# base-1.net
KiCad netlist of a schematic drawn in EAGLE
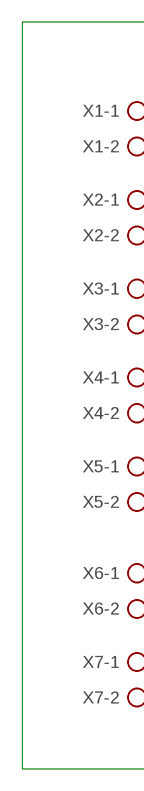
[diagram p0: schematic, sheet 1, part 1 of 2]
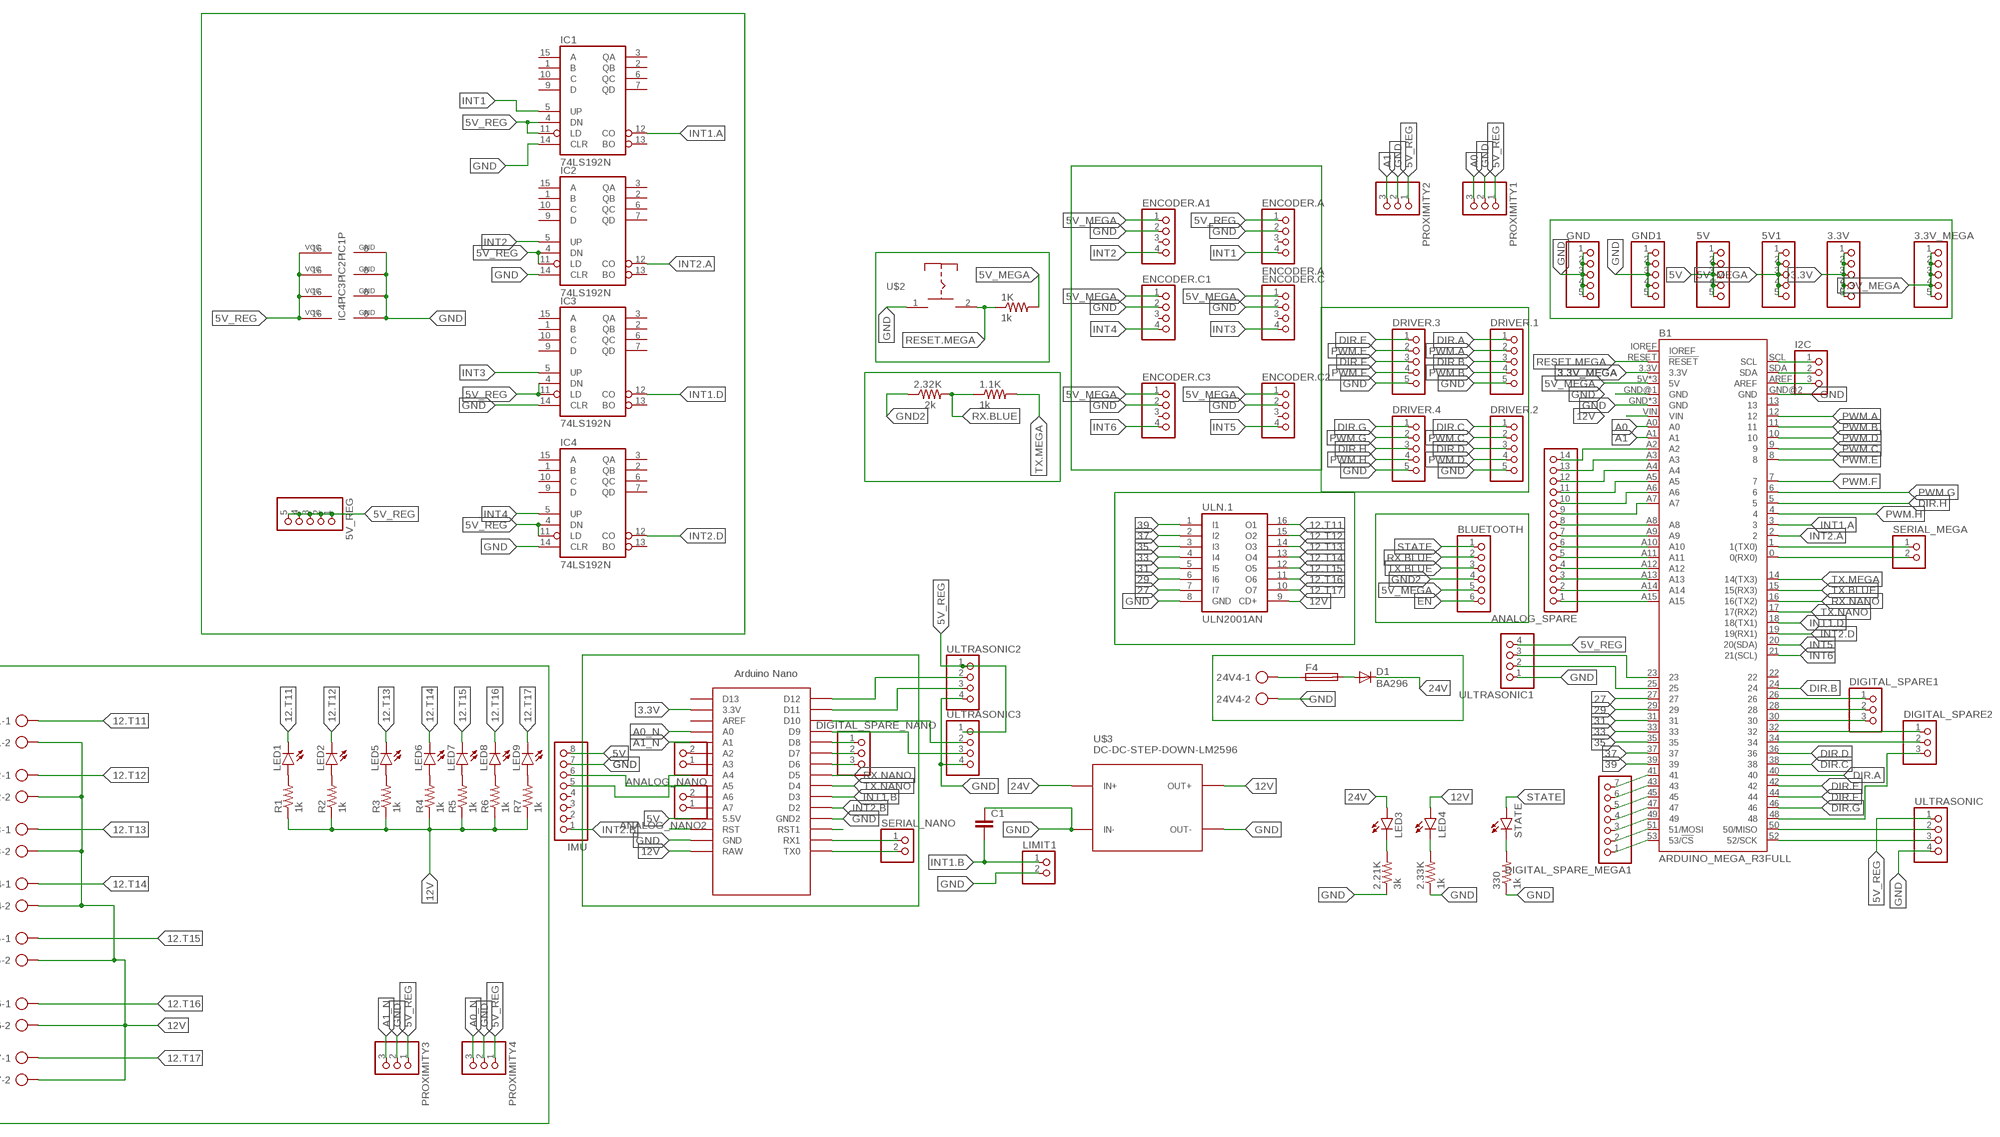
[diagram p1: schematic, sheet 1, part 2 of 2]

(export (version "E")
  (design (tool "Eeschema 10.0.6"))
  (components
    (comp (ref "1.1K")
      (value "1k")
      (footprint "eagle-import:0204_5")
      (libsource (lib "eagle-import") (part "R-US_0204/5"))
    )
    (comp (ref "1K")
      (value "1k")
      (footprint "eagle-import:0204_5")
      (libsource (lib "eagle-import") (part "R-US_0204/5"))
    )
    (comp (ref "2.21K")
      (value "3k")
      (footprint "eagle-import:0207_10")
      (libsource (lib "eagle-import") (part "R-US_0207/10"))
    )
    (comp (ref "2.32K")
      (value "2k")
      (footprint "eagle-import:0204_5")
      (libsource (lib "eagle-import") (part "R-US_0204/5"))
    )
    (comp (ref "2.33K")
      (value "1k")
      (footprint "eagle-import:0204_5")
      (libsource (lib "eagle-import") (part "R-US_0204/5"))
    )
    (comp (ref "3.3V")
      (value "PINHD-1X5")
      (footprint "eagle-import:1X05")
      (libsource (lib "eagle-import") (part "PINHD-1X5"))
    )
    (comp (ref "3.3V_MEGA")
      (value "PINHD-1X5")
      (footprint "eagle-import:1X05")
      (libsource (lib "eagle-import") (part "PINHD-1X5"))
    )
    (comp (ref "5V")
      (value "PINHD-1X5")
      (footprint "eagle-import:1X05")
      (libsource (lib "eagle-import") (part "PINHD-1X5"))
    )
    (comp (ref "5V1")
      (value "PINHD-1X5")
      (footprint "eagle-import:1X05")
      (libsource (lib "eagle-import") (part "PINHD-1X5"))
    )
    (comp (ref "5V_REG")
      (value "PINHD-1X5")
      (footprint "eagle-import:1X05")
      (libsource (lib "eagle-import") (part "PINHD-1X5"))
    )
    (comp (ref "24V4")
      (value "W237-113")
      (footprint "eagle-import:W237-113")
      (libsource (lib "eagle-import") (part "W237-113"))
    )
    (comp (ref "330")
      (value "1k")
      (footprint "eagle-import:0204_5")
      (libsource (lib "eagle-import") (part "R-US_0204/5"))
    )
    (comp (ref "ANALOG_NANO")
      (value "PINHD-1X2")
      (footprint "eagle-import:1X02")
      (libsource (lib "eagle-import") (part "PINHD-1X2"))
    )
    (comp (ref "ANALOG_NANO2")
      (value "PINHD-1X2")
      (footprint "eagle-import:1X02")
      (libsource (lib "eagle-import") (part "PINHD-1X2"))
    )
    (comp (ref "ANALOG_SPARE")
      (value "PINHD-1X14")
      (footprint "eagle-import:1X14")
      (libsource (lib "eagle-import") (part "PINHD-1X14"))
    )
    (comp (ref "B1")
      (value "ARDUINO_MEGA_R3FULL")
      (footprint "eagle-import:ARDUINO_MEGA_NO_SILK")
      (libsource (lib "eagle-import") (part "ARDUINO_MEGA_R3FULL"))
    )
    (comp (ref "BLUETOOTH")
      (value "PINHD-1X6")
      (footprint "eagle-import:1X06")
      (libsource (lib "eagle-import") (part "PINHD-1X6"))
    )
    (comp (ref "C1")
      (value "C-EU025-025X050")
      (footprint "eagle-import:C025-025X050")
      (libsource (lib "eagle-import") (part "C-EU025-025X050"))
    )
    (comp (ref "D1")
      (value "BA296")
      (footprint "eagle-import:P2-15")
      (libsource (lib "eagle-import") (part "BA296"))
    )
    (comp (ref "DIGITAL_SPARE1")
      (value "PINHD-1X3")
      (footprint "eagle-import:1X03")
      (libsource (lib "eagle-import") (part "PINHD-1X3"))
    )
    (comp (ref "DIGITAL_SPARE2")
      (value "PINHD-1X3")
      (footprint "eagle-import:1X03")
      (libsource (lib "eagle-import") (part "PINHD-1X3"))
    )
    (comp (ref "DIGITAL_SPARE_MEGA1")
      (value "PINHD-1X7")
      (footprint "eagle-import:1X07")
      (libsource (lib "eagle-import") (part "PINHD-1X7"))
    )
    (comp (ref "DIGITAL_SPARE_NANO")
      (value "PINHD-1X3")
      (footprint "eagle-import:1X03")
      (libsource (lib "eagle-import") (part "PINHD-1X3"))
    )
    (comp (ref "DRIVER.1")
      (value "PINHD-1X5")
      (footprint "eagle-import:1X05")
      (libsource (lib "eagle-import") (part "PINHD-1X5"))
    )
    (comp (ref "DRIVER.2")
      (value "PINHD-1X5")
      (footprint "eagle-import:1X05")
      (libsource (lib "eagle-import") (part "PINHD-1X5"))
    )
    (comp (ref "DRIVER.3")
      (value "PINHD-1X5")
      (footprint "eagle-import:1X05")
      (libsource (lib "eagle-import") (part "PINHD-1X5"))
    )
    (comp (ref "DRIVER.4")
      (value "PINHD-1X5")
      (footprint "eagle-import:1X05")
      (libsource (lib "eagle-import") (part "PINHD-1X5"))
    )
    (comp (ref "ENCODER.A")
      (value "ENCODER.A")
      (footprint "eagle-import:1X04")
      (libsource (lib "eagle-import") (part "PINHD-1X4"))
    )
    (comp (ref "ENCODER.A1")
      (value "PINHD-1X4")
      (footprint "eagle-import:1X04")
      (libsource (lib "eagle-import") (part "PINHD-1X4"))
    )
    (comp (ref "ENCODER.C")
      (value "PINHD-1X4")
      (footprint "eagle-import:1X04")
      (libsource (lib "eagle-import") (part "PINHD-1X4"))
    )
    (comp (ref "ENCODER.C1")
      (value "PINHD-1X4")
      (footprint "eagle-import:1X04")
      (libsource (lib "eagle-import") (part "PINHD-1X4"))
    )
    (comp (ref "ENCODER.C2")
      (value "PINHD-1X4")
      (footprint "eagle-import:1X04")
      (libsource (lib "eagle-import") (part "PINHD-1X4"))
    )
    (comp (ref "ENCODER.C3")
      (value "PINHD-1X4")
      (footprint "eagle-import:1X04")
      (libsource (lib "eagle-import") (part "PINHD-1X4"))
    )
    (comp (ref "F4")
      (value "SH22,5A")
      (footprint "eagle-import:SH22,5A")
      (fields (field (name "MPN") "0031.7701.11"))
      (libsource (lib "eagle-import") (part "SH22,5A"))
    )
    (comp (ref "GND")
      (value "PINHD-1X5")
      (footprint "eagle-import:1X05")
      (libsource (lib "eagle-import") (part "PINHD-1X5"))
    )
    (comp (ref "GND1")
      (value "PINHD-1X5")
      (footprint "eagle-import:1X05")
      (libsource (lib "eagle-import") (part "PINHD-1X5"))
    )
    (comp (ref "I2C")
      (value "PINHD-1X3")
      (footprint "eagle-import:1X03")
      (libsource (lib "eagle-import") (part "PINHD-1X3"))
    )
    (comp (ref "IC1")
      (value "74LS192N")
      (footprint "eagle-import:DIL16")
      (libsource (lib "eagle-import") (part "74192NLS"))
    )
    (comp (ref "IC2")
      (value "74LS192N")
      (footprint "eagle-import:DIL16")
      (libsource (lib "eagle-import") (part "74192NLS"))
    )
    (comp (ref "IC3")
      (value "74LS192N")
      (footprint "eagle-import:DIL16")
      (libsource (lib "eagle-import") (part "74192NLS"))
    )
    (comp (ref "IC4")
      (value "74LS192N")
      (footprint "eagle-import:DIL16")
      (libsource (lib "eagle-import") (part "74192NLS"))
    )
    (comp (ref "IMU")
      (value "PINHD-1X8")
      (footprint "eagle-import:1X08")
      (libsource (lib "eagle-import") (part "PINHD-1X8"))
    )
    (comp (ref "LED1")
      (value "LED3MM")
      (footprint "eagle-import:LED3MM")
      (libsource (lib "eagle-import") (part "LED3MM"))
    )
    (comp (ref "LED2")
      (value "LED3MM")
      (footprint "eagle-import:LED3MM")
      (libsource (lib "eagle-import") (part "LED3MM"))
    )
    (comp (ref "LED3")
      (value "LED5MM")
      (footprint "eagle-import:LED5MM")
      (libsource (lib "eagle-import") (part "LED5MM"))
    )
    (comp (ref "LED4")
      (value "LED5MM")
      (footprint "eagle-import:LED5MM")
      (libsource (lib "eagle-import") (part "LED5MM"))
    )
    (comp (ref "LED5")
      (value "LED3MM")
      (footprint "eagle-import:LED3MM")
      (libsource (lib "eagle-import") (part "LED3MM"))
    )
    (comp (ref "LED6")
      (value "LED3MM")
      (footprint "eagle-import:LED3MM")
      (libsource (lib "eagle-import") (part "LED3MM"))
    )
    (comp (ref "LED7")
      (value "LED3MM")
      (footprint "eagle-import:LED3MM")
      (libsource (lib "eagle-import") (part "LED3MM"))
    )
    (comp (ref "LED8")
      (value "LED3MM")
      (footprint "eagle-import:LED3MM")
      (libsource (lib "eagle-import") (part "LED3MM"))
    )
    (comp (ref "LED9")
      (value "LED3MM")
      (footprint "eagle-import:LED3MM")
      (libsource (lib "eagle-import") (part "LED3MM"))
    )
    (comp (ref "LIMIT1")
      (value "PINHD-1X2")
      (footprint "eagle-import:1X02")
      (libsource (lib "eagle-import") (part "PINHD-1X2"))
    )
    (comp (ref "PROXIMITY1")
      (value "PINHD-1X3")
      (footprint "eagle-import:1X03")
      (libsource (lib "eagle-import") (part "PINHD-1X3"))
    )
    (comp (ref "PROXIMITY2")
      (value "PINHD-1X3")
      (footprint "eagle-import:1X03")
      (libsource (lib "eagle-import") (part "PINHD-1X3"))
    )
    (comp (ref "PROXIMITY3")
      (value "PINHD-1X3")
      (footprint "eagle-import:1X03")
      (libsource (lib "eagle-import") (part "PINHD-1X3"))
    )
    (comp (ref "PROXIMITY4")
      (value "PINHD-1X3")
      (footprint "eagle-import:1X03")
      (libsource (lib "eagle-import") (part "PINHD-1X3"))
    )
    (comp (ref "R1")
      (value "1k")
      (footprint "eagle-import:0204_7")
      (libsource (lib "eagle-import") (part "R-US_0204/7"))
    )
    (comp (ref "R2")
      (value "1k")
      (footprint "eagle-import:0204_7")
      (libsource (lib "eagle-import") (part "R-US_0204/7"))
    )
    (comp (ref "R3")
      (value "1k")
      (footprint "eagle-import:0204_7")
      (libsource (lib "eagle-import") (part "R-US_0204/7"))
    )
    (comp (ref "R4")
      (value "1k")
      (footprint "eagle-import:0204_7")
      (libsource (lib "eagle-import") (part "R-US_0204/7"))
    )
    (comp (ref "R5")
      (value "1k")
      (footprint "eagle-import:0204_7")
      (libsource (lib "eagle-import") (part "R-US_0204/7"))
    )
    (comp (ref "R6")
      (value "1k")
      (footprint "eagle-import:0204_7")
      (libsource (lib "eagle-import") (part "R-US_0204/7"))
    )
    (comp (ref "R7")
      (value "1k")
      (footprint "eagle-import:0204_7")
      (libsource (lib "eagle-import") (part "R-US_0204/7"))
    )
    (comp (ref "SERIAL_MEGA")
      (value "PINHD-1X2")
      (footprint "eagle-import:1X02")
      (libsource (lib "eagle-import") (part "PINHD-1X2"))
    )
    (comp (ref "SERIAL_NANO")
      (value "PINHD-1X2")
      (footprint "eagle-import:1X02")
      (libsource (lib "eagle-import") (part "PINHD-1X2"))
    )
    (comp (ref "STATE")
      (value "LED3MM")
      (footprint "eagle-import:LED3MM")
      (libsource (lib "eagle-import") (part "LED3MM"))
    )
    (comp (ref "U$1")
      (value "NANO")
      (footprint "eagle-import:NANO")
      (libsource (lib "eagle-import") (part "NANO"))
    )
    (comp (ref "U$2")
      (value "PUSHBOTTON")
      (footprint "eagle-import:PUSHBOTTON")
      (libsource (lib "eagle-import") (part "PUSHBOTTON"))
    )
    (comp (ref "U$3")
      (value "DC-DC-STEP-DOWN-LM2596")
      (footprint "eagle-import:DC-DC-STEP-DOWN-LM2596")
      (libsource (lib "eagle-import") (part "DC-DC-STEP-DOWN-LM2596"))
    )
    (comp (ref "ULN.1")
      (value "ULN2001AN")
      (footprint "eagle-import:DIL16")
      (libsource (lib "eagle-import") (part "ULN2001AN"))
    )
    (comp (ref "ULTRASONIC")
      (value "PINHD-1X4")
      (footprint "eagle-import:1X04")
      (libsource (lib "eagle-import") (part "PINHD-1X4"))
    )
    (comp (ref "ULTRASONIC1")
      (value "PINHD-1X4")
      (footprint "eagle-import:1X04")
      (libsource (lib "eagle-import") (part "PINHD-1X4"))
    )
    (comp (ref "ULTRASONIC2")
      (value "PINHD-1X4")
      (footprint "eagle-import:1X04")
      (libsource (lib "eagle-import") (part "PINHD-1X4"))
    )
    (comp (ref "ULTRASONIC3")
      (value "PINHD-1X4")
      (footprint "eagle-import:1X04")
      (libsource (lib "eagle-import") (part "PINHD-1X4"))
    )
    (comp (ref "X1")
      (value "AK300/2")
      (footprint "eagle-import:AK300_2")
      (libsource (lib "eagle-import") (part "AK300/2"))
    )
    (comp (ref "X2")
      (value "AK300/2")
      (footprint "eagle-import:AK300_2")
      (libsource (lib "eagle-import") (part "AK300/2"))
    )
    (comp (ref "X3")
      (value "AK300/2")
      (footprint "eagle-import:AK300_2")
      (libsource (lib "eagle-import") (part "AK300/2"))
    )
    (comp (ref "X4")
      (value "AK300/2")
      (footprint "eagle-import:AK300_2")
      (libsource (lib "eagle-import") (part "AK300/2"))
    )
    (comp (ref "X5")
      (value "AK300/2")
      (footprint "eagle-import:AK300_2")
      (libsource (lib "eagle-import") (part "AK300/2"))
    )
    (comp (ref "X6")
      (value "AK300/2")
      (footprint "eagle-import:AK300_2")
      (libsource (lib "eagle-import") (part "AK300/2"))
    )
    (comp (ref "X7")
      (value "AK300/2")
      (footprint "eagle-import:AK300_2")
      (libsource (lib "eagle-import") (part "AK300/2"))
    )
  )
  (nets
    (net (code "1") (name "3.3V") (class "Default")
      (node (ref "3.3V") (pin "1") (pinfunction "1_1") (pintype "passive"))
      (node (ref "3.3V") (pin "2") (pinfunction "2_2") (pintype "passive"))
      (node (ref "3.3V") (pin "3") (pinfunction "3_3") (pintype "passive"))
      (node (ref "3.3V") (pin "4") (pinfunction "4_4") (pintype "passive"))
      (node (ref "3.3V") (pin "5") (pinfunction "5_5") (pintype "passive"))
      (node (ref "U$1") (pin "3.3V") (pinfunction "3.3V_3.3V") (pintype "bidirectional"))
    )
    (net (code "2") (name "3.3V_MEGA") (class "Default")
      (node (ref "3.3V_MEGA") (pin "1") (pinfunction "1_1") (pintype "passive"))
      (node (ref "3.3V_MEGA") (pin "2") (pinfunction "2_2") (pintype "passive"))
      (node (ref "3.3V_MEGA") (pin "3") (pinfunction "3_3") (pintype "passive"))
      (node (ref "3.3V_MEGA") (pin "4") (pinfunction "4_4") (pintype "passive"))
      (node (ref "3.3V_MEGA") (pin "5") (pinfunction "5_5") (pintype "passive"))
      (node (ref "B1") (pin "3.3V") (pinfunction "3.3V_3.3V") (pintype "bidirectional"))
    )
    (net (code "3") (name "5V") (class "Default")
      (node (ref "5V") (pin "1") (pinfunction "1_1") (pintype "passive"))
      (node (ref "5V") (pin "2") (pinfunction "2_2") (pintype "passive"))
      (node (ref "5V") (pin "3") (pinfunction "3_3") (pintype "passive"))
      (node (ref "5V") (pin "4") (pinfunction "4_4") (pintype "passive"))
      (node (ref "5V") (pin "5") (pinfunction "5_5") (pintype "passive"))
      (node (ref "IMU") (pin "8") (pinfunction "8_8") (pintype "passive"))
      (node (ref "U$1") (pin "5V") (pinfunction "5.5V_5V") (pintype "bidirectional"))
    )
    (net (code "4") (name "5V_MEGA") (class "Default")
      (node (ref "1K") (pin "2") (pinfunction "2_2") (pintype "passive"))
      (node (ref "5V1") (pin "1") (pinfunction "1_1") (pintype "passive"))
      (node (ref "5V1") (pin "2") (pinfunction "2_2") (pintype "passive"))
      (node (ref "5V1") (pin "3") (pinfunction "3_3") (pintype "passive"))
      (node (ref "5V1") (pin "4") (pinfunction "4_4") (pintype "passive"))
      (node (ref "5V1") (pin "5") (pinfunction "5_5") (pintype "passive"))
      (node (ref "B1") (pin "5V") (pinfunction "5V_5V") (pintype "bidirectional"))
      (node (ref "B1") (pin "5V@1") (pinfunction "5V_5V@1") (pintype "bidirectional"))
      (node (ref "B1") (pin "5V@2") (pinfunction "5V_5V@2") (pintype "bidirectional"))
      (node (ref "BLUETOOTH") (pin "5") (pinfunction "5_5") (pintype "passive"))
      (node (ref "ENCODER.A1") (pin "1") (pinfunction "1_1") (pintype "passive"))
      (node (ref "ENCODER.C") (pin "1") (pinfunction "1_1") (pintype "passive"))
      (node (ref "ENCODER.C1") (pin "1") (pinfunction "1_1") (pintype "passive"))
      (node (ref "ENCODER.C2") (pin "1") (pinfunction "1_1") (pintype "passive"))
      (node (ref "ENCODER.C3") (pin "1") (pinfunction "1_1") (pintype "passive"))
    )
    (net (code "5") (name "5V_REG") (class "Default")
      (node (ref "5V_REG") (pin "1") (pinfunction "1_1") (pintype "passive"))
      (node (ref "5V_REG") (pin "2") (pinfunction "2_2") (pintype "passive"))
      (node (ref "5V_REG") (pin "3") (pinfunction "3_3") (pintype "passive"))
      (node (ref "5V_REG") (pin "4") (pinfunction "4_4") (pintype "passive"))
      (node (ref "5V_REG") (pin "5") (pinfunction "5_5") (pintype "passive"))
      (node (ref "ENCODER.A") (pin "1") (pinfunction "1_1") (pintype "passive"))
      (node (ref "IC1") (pin "11") (pinfunction "LD_11") (pintype "input"))
      (node (ref "IC1") (pin "16") (pinfunction "VCC_16") (pintype "power_in"))
      (node (ref "IC1") (pin "4") (pinfunction "DN_4") (pintype "input"))
      (node (ref "IC2") (pin "11") (pinfunction "LD_11") (pintype "input"))
      (node (ref "IC2") (pin "16") (pinfunction "VCC_16") (pintype "power_in"))
      (node (ref "IC2") (pin "4") (pinfunction "DN_4") (pintype "input"))
      (node (ref "IC3") (pin "11") (pinfunction "LD_11") (pintype "input"))
      (node (ref "IC3") (pin "16") (pinfunction "VCC_16") (pintype "power_in"))
      (node (ref "IC3") (pin "4") (pinfunction "DN_4") (pintype "input"))
      (node (ref "IC4") (pin "11") (pinfunction "LD_11") (pintype "input"))
      (node (ref "IC4") (pin "16") (pinfunction "VCC_16") (pintype "power_in"))
      (node (ref "IC4") (pin "4") (pinfunction "DN_4") (pintype "input"))
      (node (ref "PROXIMITY1") (pin "1") (pinfunction "1_1") (pintype "passive"))
      (node (ref "PROXIMITY2") (pin "1") (pinfunction "1_1") (pintype "passive"))
      (node (ref "PROXIMITY3") (pin "1") (pinfunction "1_1") (pintype "passive"))
      (node (ref "PROXIMITY4") (pin "1") (pinfunction "1_1") (pintype "passive"))
      (node (ref "ULTRASONIC") (pin "1") (pinfunction "1_1") (pintype "passive"))
      (node (ref "ULTRASONIC1") (pin "4") (pinfunction "4_4") (pintype "passive"))
      (node (ref "ULTRASONIC2") (pin "1") (pinfunction "1_1") (pintype "passive"))
      (node (ref "ULTRASONIC3") (pin "1") (pinfunction "1_1") (pintype "passive"))
    )
    (net (code "6") (name "12.T11") (class "Default")
      (node (ref "LED1") (pin "K") (pinfunction "C_K") (pintype "passive"))
      (node (ref "ULN.1") (pin "16") (pinfunction "O1_16") (pintype "open_collector"))
      (node (ref "X1") (pin "1") (pinfunction "KL_1") (pintype "passive"))
    )
    (net (code "7") (name "12.T12") (class "Default")
      (node (ref "LED2") (pin "K") (pinfunction "C_K") (pintype "passive"))
      (node (ref "ULN.1") (pin "15") (pinfunction "O2_15") (pintype "open_collector"))
      (node (ref "X2") (pin "1") (pinfunction "KL_1") (pintype "passive"))
    )
    (net (code "8") (name "12.T13") (class "Default")
      (node (ref "LED5") (pin "K") (pinfunction "C_K") (pintype "passive"))
      (node (ref "ULN.1") (pin "14") (pinfunction "O3_14") (pintype "open_collector"))
      (node (ref "X3") (pin "1") (pinfunction "KL_1") (pintype "passive"))
    )
    (net (code "9") (name "12.T14") (class "Default")
      (node (ref "LED6") (pin "K") (pinfunction "C_K") (pintype "passive"))
      (node (ref "ULN.1") (pin "13") (pinfunction "O4_13") (pintype "open_collector"))
      (node (ref "X4") (pin "1") (pinfunction "KL_1") (pintype "passive"))
    )
    (net (code "10") (name "12.T15") (class "Default")
      (node (ref "LED7") (pin "K") (pinfunction "C_K") (pintype "passive"))
      (node (ref "ULN.1") (pin "12") (pinfunction "O5_12") (pintype "open_collector"))
      (node (ref "X5") (pin "1") (pinfunction "KL_1") (pintype "passive"))
    )
    (net (code "11") (name "12.T16") (class "Default")
      (node (ref "LED8") (pin "K") (pinfunction "C_K") (pintype "passive"))
      (node (ref "ULN.1") (pin "11") (pinfunction "O6_11") (pintype "open_collector"))
      (node (ref "X6") (pin "1") (pinfunction "KL_1") (pintype "passive"))
    )
    (net (code "12") (name "12.T17") (class "Default")
      (node (ref "LED9") (pin "K") (pinfunction "C_K") (pintype "passive"))
      (node (ref "ULN.1") (pin "10") (pinfunction "O7_10") (pintype "open_collector"))
      (node (ref "X7") (pin "1") (pinfunction "KL_1") (pintype "passive"))
    )
    (net (code "13") (name "12V") (class "Default")
      (node (ref "B1") (pin "VIN") (pinfunction "VIN_VIN") (pintype "bidirectional"))
      (node (ref "LED4") (pin "A") (pinfunction "A_A") (pintype "passive"))
      (node (ref "R1") (pin "1") (pinfunction "1_1") (pintype "passive"))
      (node (ref "R2") (pin "1") (pinfunction "1_1") (pintype "passive"))
      (node (ref "R3") (pin "1") (pinfunction "1_1") (pintype "passive"))
      (node (ref "R4") (pin "1") (pinfunction "1_1") (pintype "passive"))
      (node (ref "R5") (pin "1") (pinfunction "1_1") (pintype "passive"))
      (node (ref "R6") (pin "1") (pinfunction "1_1") (pintype "passive"))
      (node (ref "R7") (pin "1") (pinfunction "1_1") (pintype "passive"))
      (node (ref "U$1") (pin "RAW") (pinfunction "RAW_RAW") (pintype "bidirectional"))
      (node (ref "U$3") (pin "OUT+") (pinfunction "OUT+_OUT+") (pintype "bidirectional"))
      (node (ref "ULN.1") (pin "9") (pinfunction "CD+_9") (pintype "passive"))
      (node (ref "X1") (pin "2") (pinfunction "KL_2") (pintype "passive"))
      (node (ref "X2") (pin "2") (pinfunction "KL_2") (pintype "passive"))
      (node (ref "X3") (pin "2") (pinfunction "KL_2") (pintype "passive"))
      (node (ref "X4") (pin "2") (pinfunction "KL_2") (pintype "passive"))
      (node (ref "X5") (pin "2") (pinfunction "KL_2") (pintype "passive"))
      (node (ref "X6") (pin "2") (pinfunction "KL_2") (pintype "passive"))
      (node (ref "X7") (pin "2") (pinfunction "KL_2") (pintype "passive"))
    )
    (net (code "14") (name "24V") (class "Default")
      (node (ref "D1") (pin "C") (pinfunction "C_C") (pintype "passive"))
      (node (ref "LED3") (pin "A") (pinfunction "A_A") (pintype "passive"))
      (node (ref "U$3") (pin "IN+") (pinfunction "IN+_IN+") (pintype "bidirectional"))
    )
    (net (code "15") (name "27") (class "Default")
      (node (ref "B1") (pin "27") (pinfunction "27_27") (pintype "bidirectional"))
      (node (ref "ULN.1") (pin "7") (pinfunction "I7_7") (pintype "input"))
    )
    (net (code "16") (name "29") (class "Default")
      (node (ref "B1") (pin "29") (pinfunction "29_29") (pintype "bidirectional"))
      (node (ref "ULN.1") (pin "6") (pinfunction "I6_6") (pintype "input"))
    )
    (net (code "17") (name "31") (class "Default")
      (node (ref "B1") (pin "31") (pinfunction "31_31") (pintype "bidirectional"))
      (node (ref "ULN.1") (pin "5") (pinfunction "I5_5") (pintype "input"))
    )
    (net (code "18") (name "33") (class "Default")
      (node (ref "B1") (pin "33") (pinfunction "33_33") (pintype "bidirectional"))
      (node (ref "ULN.1") (pin "4") (pinfunction "I4_4") (pintype "input"))
    )
    (net (code "19") (name "35") (class "Default")
      (node (ref "B1") (pin "35") (pinfunction "35_35") (pintype "bidirectional"))
      (node (ref "ULN.1") (pin "3") (pinfunction "I3_3") (pintype "input"))
    )
    (net (code "20") (name "37") (class "Default")
      (node (ref "B1") (pin "37") (pinfunction "37_37") (pintype "bidirectional"))
      (node (ref "ULN.1") (pin "2") (pinfunction "I2_2") (pintype "input"))
    )
    (net (code "21") (name "39") (class "Default")
      (node (ref "B1") (pin "39") (pinfunction "39_39") (pintype "bidirectional"))
      (node (ref "ULN.1") (pin "1") (pinfunction "I1_1") (pintype "input"))
    )
    (net (code "22") (name "A0") (class "Default")
      (node (ref "B1") (pin "A0") (pinfunction "A0_A0") (pintype "bidirectional"))
      (node (ref "PROXIMITY1") (pin "3") (pinfunction "3_3") (pintype "passive"))
    )
    (net (code "23") (name "A0_N") (class "Default")
      (node (ref "PROXIMITY4") (pin "3") (pinfunction "3_3") (pintype "passive"))
      (node (ref "U$1") (pin "A0") (pinfunction "A0_A0") (pintype "bidirectional"))
    )
    (net (code "24") (name "A1") (class "Default")
      (node (ref "B1") (pin "A1") (pinfunction "A1_A1") (pintype "bidirectional"))
      (node (ref "PROXIMITY2") (pin "3") (pinfunction "3_3") (pintype "passive"))
    )
    (net (code "25") (name "A1_N") (class "Default")
      (node (ref "PROXIMITY3") (pin "3") (pinfunction "3_3") (pintype "passive"))
      (node (ref "U$1") (pin "A1") (pinfunction "A1_A1") (pintype "bidirectional"))
    )
    (net (code "26") (name "DIR.A") (class "Default")
      (node (ref "B1") (pin "40") (pinfunction "40_40") (pintype "bidirectional"))
      (node (ref "DRIVER.1") (pin "1") (pinfunction "1_1") (pintype "passive"))
    )
    (net (code "27") (name "DIR.B") (class "Default")
      (node (ref "B1") (pin "24") (pinfunction "24_24") (pintype "bidirectional"))
      (node (ref "DRIVER.1") (pin "3") (pinfunction "3_3") (pintype "passive"))
    )
    (net (code "28") (name "DIR.C") (class "Default")
      (node (ref "B1") (pin "38") (pinfunction "38_38") (pintype "bidirectional"))
      (node (ref "DRIVER.2") (pin "1") (pinfunction "1_1") (pintype "passive"))
    )
    (net (code "29") (name "DIR.D") (class "Default")
      (node (ref "B1") (pin "36") (pinfunction "36_36") (pintype "bidirectional"))
      (node (ref "DRIVER.2") (pin "3") (pinfunction "3_3") (pintype "passive"))
    )
    (net (code "30") (name "DIR.E") (class "Default")
      (node (ref "B1") (pin "42") (pinfunction "42_42") (pintype "bidirectional"))
      (node (ref "DRIVER.3") (pin "1") (pinfunction "1_1") (pintype "passive"))
    )
    (net (code "31") (name "DIR.F") (class "Default")
      (node (ref "B1") (pin "44") (pinfunction "44_44") (pintype "bidirectional"))
      (node (ref "DRIVER.3") (pin "3") (pinfunction "3_3") (pintype "passive"))
    )
    (net (code "32") (name "DIR.G") (class "Default")
      (node (ref "B1") (pin "46") (pinfunction "46_46") (pintype "bidirectional"))
      (node (ref "DRIVER.4") (pin "1") (pinfunction "1_1") (pintype "passive"))
    )
    (net (code "33") (name "DIR.H") (class "Default")
      (node (ref "B1") (pin "5") (pinfunction "5_5") (pintype "bidirectional"))
      (node (ref "DRIVER.4") (pin "3") (pinfunction "3_3") (pintype "passive"))
    )
    (net (code "34") (name "EN") (class "Default")
      (node (ref "BLUETOOTH") (pin "6") (pinfunction "6_6") (pintype "passive"))
    )
    (net (code "35") (name "GND") (class "Default")
      (node (ref "2.21K") (pin "1") (pinfunction "1_1") (pintype "passive"))
      (node (ref "2.33K") (pin "1") (pinfunction "1_1") (pintype "passive"))
      (node (ref "24V4") (pin "2") (pinfunction "KL_2") (pintype "passive"))
      (node (ref "330") (pin "1") (pinfunction "1_1") (pintype "passive"))
      (node (ref "B1") (pin "GND") (pinfunction "GND_GND") (pintype "bidirectional"))
      (node (ref "B1") (pin "GND@1") (pinfunction "GND_GND@1") (pintype "bidirectional"))
      (node (ref "B1") (pin "GND@2") (pinfunction "GND_GND@2") (pintype "bidirectional"))
      (node (ref "B1") (pin "GND@3") (pinfunction "GND_GND@3") (pintype "bidirectional"))
      (node (ref "B1") (pin "GND@4") (pinfunction "GND_GND@4") (pintype "bidirectional"))
      (node (ref "C1") (pin "1") (pinfunction "1_1") (pintype "passive"))
      (node (ref "DRIVER.1") (pin "5") (pinfunction "5_5") (pintype "passive"))
      (node (ref "DRIVER.2") (pin "5") (pinfunction "5_5") (pintype "passive"))
      (node (ref "DRIVER.3") (pin "5") (pinfunction "5_5") (pintype "passive"))
      (node (ref "DRIVER.4") (pin "5") (pinfunction "5_5") (pintype "passive"))
      (node (ref "ENCODER.A") (pin "2") (pinfunction "2_2") (pintype "passive"))
      (node (ref "ENCODER.A1") (pin "2") (pinfunction "2_2") (pintype "passive"))
      (node (ref "ENCODER.C") (pin "2") (pinfunction "2_2") (pintype "passive"))
      (node (ref "ENCODER.C1") (pin "2") (pinfunction "2_2") (pintype "passive"))
      (node (ref "ENCODER.C2") (pin "2") (pinfunction "2_2") (pintype "passive"))
      (node (ref "ENCODER.C3") (pin "2") (pinfunction "2_2") (pintype "passive"))
      (node (ref "GND") (pin "1") (pinfunction "1_1") (pintype "passive"))
      (node (ref "GND") (pin "2") (pinfunction "2_2") (pintype "passive"))
      (node (ref "GND") (pin "3") (pinfunction "3_3") (pintype "passive"))
      (node (ref "GND") (pin "4") (pinfunction "4_4") (pintype "passive"))
      (node (ref "GND") (pin "5") (pinfunction "5_5") (pintype "passive"))
      (node (ref "GND1") (pin "1") (pinfunction "1_1") (pintype "passive"))
      (node (ref "GND1") (pin "2") (pinfunction "2_2") (pintype "passive"))
      (node (ref "GND1") (pin "3") (pinfunction "3_3") (pintype "passive"))
      (node (ref "GND1") (pin "4") (pinfunction "4_4") (pintype "passive"))
      (node (ref "GND1") (pin "5") (pinfunction "5_5") (pintype "passive"))
      (node (ref "IC1") (pin "14") (pinfunction "CLR_14") (pintype "input"))
      (node (ref "IC1") (pin "8") (pinfunction "GND_8") (pintype "power_in"))
      (node (ref "IC2") (pin "14") (pinfunction "CLR_14") (pintype "input"))
      (node (ref "IC2") (pin "8") (pinfunction "GND_8") (pintype "power_in"))
      (node (ref "IC3") (pin "14") (pinfunction "CLR_14") (pintype "input"))
      (node (ref "IC3") (pin "8") (pinfunction "GND_8") (pintype "power_in"))
      (node (ref "IC4") (pin "14") (pinfunction "CLR_14") (pintype "input"))
      (node (ref "IC4") (pin "8") (pinfunction "GND_8") (pintype "power_in"))
      (node (ref "IMU") (pin "7") (pinfunction "7_7") (pintype "passive"))
      (node (ref "LIMIT1") (pin "2") (pinfunction "2_2") (pintype "passive"))
      (node (ref "PROXIMITY1") (pin "2") (pinfunction "2_2") (pintype "passive"))
      (node (ref "PROXIMITY2") (pin "2") (pinfunction "2_2") (pintype "passive"))
      (node (ref "PROXIMITY3") (pin "2") (pinfunction "2_2") (pintype "passive"))
      (node (ref "PROXIMITY4") (pin "2") (pinfunction "2_2") (pintype "passive"))
      (node (ref "U$1") (pin "GND") (pinfunction "GND_GND") (pintype "bidirectional"))
      (node (ref "U$1") (pin "GND1") (pinfunction "GND2_GND1") (pintype "bidirectional"))
      (node (ref "U$2") (pin "1") (pinfunction "1_1") (pintype "bidirectional"))
      (node (ref "U$3") (pin "IN-") (pinfunction "IN-_IN-") (pintype "bidirectional"))
      (node (ref "U$3") (pin "OUT-") (pinfunction "OUT-_OUT-") (pintype "bidirectional"))
      (node (ref "ULN.1") (pin "8") (pinfunction "GND_8") (pintype "power_in"))
      (node (ref "ULTRASONIC") (pin "4") (pinfunction "4_4") (pintype "passive"))
      (node (ref "ULTRASONIC1") (pin "1") (pinfunction "1_1") (pintype "passive"))
      (node (ref "ULTRASONIC2") (pin "4") (pinfunction "4_4") (pintype "passive"))
      (node (ref "ULTRASONIC3") (pin "4") (pinfunction "4_4") (pintype "passive"))
    )
    (net (code "36") (name "GND2") (class "Default")
      (node (ref "2.32K") (pin "1") (pinfunction "1_1") (pintype "passive"))
      (node (ref "BLUETOOTH") (pin "4") (pinfunction "4_4") (pintype "passive"))
    )
    (net (code "37") (name "INT1") (class "Default")
      (node (ref "ENCODER.A") (pin "4") (pinfunction "4_4") (pintype "passive"))
      (node (ref "IC1") (pin "5") (pinfunction "UP_5") (pintype "input"))
    )
    (net (code "38") (name "INT1.A") (class "Default")
      (node (ref "B1") (pin "3") (pinfunction "3_3") (pintype "bidirectional"))
      (node (ref "IC1") (pin "12") (pinfunction "CO_12") (pintype "output"))
    )
    (net (code "39") (name "INT1.B") (class "Default")
      (node (ref "C1") (pin "2") (pinfunction "2_2") (pintype "passive"))
      (node (ref "LIMIT1") (pin "1") (pinfunction "1_1") (pintype "passive"))
      (node (ref "U$1") (pin "D3") (pinfunction "D3_D3") (pintype "bidirectional"))
    )
    (net (code "40") (name "INT1.D") (class "Default")
      (node (ref "B1") (pin "18") (pinfunction "18(TX1)_18") (pintype "bidirectional"))
      (node (ref "IC3") (pin "12") (pinfunction "CO_12") (pintype "output"))
    )
    (net (code "41") (name "INT2") (class "Default")
      (node (ref "ENCODER.A1") (pin "4") (pinfunction "4_4") (pintype "passive"))
      (node (ref "IC2") (pin "5") (pinfunction "UP_5") (pintype "input"))
    )
    (net (code "42") (name "INT2.A") (class "Default")
      (node (ref "B1") (pin "2") (pinfunction "2_2") (pintype "bidirectional"))
      (node (ref "IC2") (pin "12") (pinfunction "CO_12") (pintype "output"))
    )
    (net (code "43") (name "INT2.B") (class "Default")
      (node (ref "IMU") (pin "1") (pinfunction "1_1") (pintype "passive"))
      (node (ref "U$1") (pin "D2") (pinfunction "D2_D2") (pintype "bidirectional"))
    )
    (net (code "44") (name "INT2.D") (class "Default")
      (node (ref "B1") (pin "19") (pinfunction "19(RX1)_19") (pintype "bidirectional"))
      (node (ref "IC4") (pin "12") (pinfunction "CO_12") (pintype "output"))
    )
    (net (code "45") (name "INT3") (class "Default")
      (node (ref "ENCODER.C") (pin "4") (pinfunction "4_4") (pintype "passive"))
      (node (ref "IC3") (pin "5") (pinfunction "UP_5") (pintype "input"))
    )
    (net (code "46") (name "INT4") (class "Default")
      (node (ref "ENCODER.C1") (pin "4") (pinfunction "4_4") (pintype "passive"))
      (node (ref "IC4") (pin "5") (pinfunction "UP_5") (pintype "input"))
    )
    (net (code "47") (name "INT5") (class "Default")
      (node (ref "B1") (pin "20") (pinfunction "20(SDA)_20") (pintype "bidirectional"))
      (node (ref "ENCODER.C2") (pin "4") (pinfunction "4_4") (pintype "passive"))
    )
    (net (code "48") (name "INT6") (class "Default")
      (node (ref "B1") (pin "21") (pinfunction "21(SCL)_21") (pintype "bidirectional"))
      (node (ref "ENCODER.C3") (pin "4") (pinfunction "4_4") (pintype "passive"))
    )
    (net (code "49") (name "Net-(24V4A-KL)") (class "Default")
      (node (ref "24V4") (pin "1") (pinfunction "KL_1") (pintype "passive"))
      (node (ref "F4") (pin "1") (pinfunction "1_1") (pintype "passive"))
    )
    (net (code "50") (name "Net-(ANALOG_NANO-Pad1)") (class "Default")
      (node (ref "ANALOG_NANO") (pin "1") (pinfunction "1_1") (pintype "passive"))
      (node (ref "U$1") (pin "A3") (pinfunction "A3_A3") (pintype "bidirectional"))
    )
    (net (code "51") (name "Net-(ANALOG_NANO-Pad2)") (class "Default")
      (node (ref "ANALOG_NANO") (pin "2") (pinfunction "2_2") (pintype "passive"))
      (node (ref "U$1") (pin "A2") (pinfunction "A2_A2") (pintype "bidirectional"))
    )
    (net (code "52") (name "Net-(ANALOG_NANO2-Pad1)") (class "Default")
      (node (ref "ANALOG_NANO2") (pin "1") (pinfunction "1_1") (pintype "passive"))
      (node (ref "U$1") (pin "A7") (pinfunction "A7_A7") (pintype "bidirectional"))
    )
    (net (code "53") (name "Net-(ANALOG_NANO2-Pad2)") (class "Default")
      (node (ref "ANALOG_NANO2") (pin "2") (pinfunction "2_2") (pintype "passive"))
      (node (ref "U$1") (pin "A6") (pinfunction "A6_A6") (pintype "bidirectional"))
    )
    (net (code "54") (name "Net-(ANALOG_SPARE-Pad1)") (class "Default")
      (node (ref "ANALOG_SPARE") (pin "1") (pinfunction "1_1") (pintype "passive"))
      (node (ref "B1") (pin "A15") (pinfunction "A15_A15") (pintype "bidirectional"))
    )
    (net (code "55") (name "Net-(ANALOG_SPARE-Pad2)") (class "Default")
      (node (ref "ANALOG_SPARE") (pin "2") (pinfunction "2_2") (pintype "passive"))
      (node (ref "B1") (pin "A14") (pinfunction "A14_A14") (pintype "bidirectional"))
    )
    (net (code "56") (name "Net-(ANALOG_SPARE-Pad3)") (class "Default")
      (node (ref "ANALOG_SPARE") (pin "3") (pinfunction "3_3") (pintype "passive"))
      (node (ref "B1") (pin "A13") (pinfunction "A13_A13") (pintype "bidirectional"))
    )
    (net (code "57") (name "Net-(ANALOG_SPARE-Pad4)") (class "Default")
      (node (ref "ANALOG_SPARE") (pin "4") (pinfunction "4_4") (pintype "passive"))
      (node (ref "B1") (pin "A12") (pinfunction "A12_A12") (pintype "bidirectional"))
    )
    (net (code "58") (name "Net-(ANALOG_SPARE-Pad5)") (class "Default")
      (node (ref "ANALOG_SPARE") (pin "5") (pinfunction "5_5") (pintype "passive"))
      (node (ref "B1") (pin "A11") (pinfunction "A11_A11") (pintype "bidirectional"))
    )
    (net (code "59") (name "Net-(ANALOG_SPARE-Pad6)") (class "Default")
      (node (ref "ANALOG_SPARE") (pin "6") (pinfunction "6_6") (pintype "passive"))
      (node (ref "B1") (pin "A10") (pinfunction "A10_A10") (pintype "bidirectional"))
    )
    (net (code "60") (name "Net-(ANALOG_SPARE-Pad7)") (class "Default")
      (node (ref "ANALOG_SPARE") (pin "7") (pinfunction "7_7") (pintype "passive"))
      (node (ref "B1") (pin "A9") (pinfunction "A9_A9") (pintype "bidirectional"))
    )
    (net (code "61") (name "Net-(ANALOG_SPARE-Pad8)") (class "Default")
      (node (ref "ANALOG_SPARE") (pin "8") (pinfunction "8_8") (pintype "passive"))
      (node (ref "B1") (pin "A8") (pinfunction "A8_A8") (pintype "bidirectional"))
    )
    (net (code "62") (name "Net-(ANALOG_SPARE-Pad9)") (class "Default")
      (node (ref "ANALOG_SPARE") (pin "9") (pinfunction "9_9") (pintype "passive"))
      (node (ref "B1") (pin "A7") (pinfunction "A7_A7") (pintype "bidirectional"))
    )
    (net (code "63") (name "Net-(ANALOG_SPARE-Pad10)") (class "Default")
      (node (ref "ANALOG_SPARE") (pin "10") (pinfunction "10_10") (pintype "passive"))
      (node (ref "B1") (pin "A6") (pinfunction "A6_A6") (pintype "bidirectional"))
    )
    (net (code "64") (name "Net-(ANALOG_SPARE-Pad11)") (class "Default")
      (node (ref "ANALOG_SPARE") (pin "11") (pinfunction "11_11") (pintype "passive"))
      (node (ref "B1") (pin "A5") (pinfunction "A5_A5") (pintype "bidirectional"))
    )
    (net (code "65") (name "Net-(ANALOG_SPARE-Pad12)") (class "Default")
      (node (ref "ANALOG_SPARE") (pin "12") (pinfunction "12_12") (pintype "passive"))
      (node (ref "B1") (pin "A4") (pinfunction "A4_A4") (pintype "bidirectional"))
    )
    (net (code "66") (name "Net-(ANALOG_SPARE-Pad13)") (class "Default")
      (node (ref "ANALOG_SPARE") (pin "13") (pinfunction "13_13") (pintype "passive"))
      (node (ref "B1") (pin "A3") (pinfunction "A3_A3") (pintype "bidirectional"))
    )
    (net (code "67") (name "Net-(ANALOG_SPARE-Pad14)") (class "Default")
      (node (ref "ANALOG_SPARE") (pin "14") (pinfunction "14_14") (pintype "passive"))
      (node (ref "B1") (pin "A2") (pinfunction "A2_A2") (pintype "bidirectional"))
    )
    (net (code "68") (name "Net-(B1-0(RX0))") (class "Default")
      (node (ref "B1") (pin "0") (pinfunction "0(RX0)_0") (pintype "bidirectional"))
      (node (ref "SERIAL_MEGA") (pin "2") (pinfunction "2_2") (pintype "passive"))
    )
    (net (code "69") (name "Net-(B1-1(TX0))") (class "Default")
      (node (ref "B1") (pin "1") (pinfunction "1(TX0)_1") (pintype "bidirectional"))
      (node (ref "SERIAL_MEGA") (pin "1") (pinfunction "1_1") (pintype "passive"))
    )
    (net (code "70") (name "Net-(B1-50{slash}MISO)") (class "Default")
      (node (ref "B1") (pin "50") (pinfunction "50/MISO_50") (pintype "bidirectional"))
      (node (ref "ULTRASONIC") (pin "2") (pinfunction "2_2") (pintype "passive"))
    )
    (net (code "71") (name "Net-(B1-51{slash}MOSI)") (class "Default")
      (node (ref "B1") (pin "51") (pinfunction "51/MOSI_51") (pintype "bidirectional"))
      (node (ref "DIGITAL_SPARE_MEGA1") (pin "2") (pinfunction "2_2") (pintype "passive"))
    )
    (net (code "72") (name "Net-(B1-52{slash}SCK)") (class "Default")
      (node (ref "B1") (pin "52") (pinfunction "52/SCK_52") (pintype "bidirectional"))
      (node (ref "ULTRASONIC") (pin "3") (pinfunction "3_3") (pintype "passive"))
    )
    (net (code "73") (name "Net-(B1-53{slash}~{CS})") (class "Default")
      (node (ref "B1") (pin "53") (pinfunction "53/~{CS}_53") (pintype "bidirectional"))
      (node (ref "DIGITAL_SPARE_MEGA1") (pin "1") (pinfunction "1_1") (pintype "passive"))
    )
    (net (code "74") (name "Net-(B1-Pad23)") (class "Default")
      (node (ref "B1") (pin "23") (pinfunction "23_23") (pintype "bidirectional"))
      (node (ref "ULTRASONIC1") (pin "3") (pinfunction "3_3") (pintype "passive"))
    )
    (net (code "75") (name "Net-(B1-Pad25)") (class "Default")
      (node (ref "B1") (pin "25") (pinfunction "25_25") (pintype "bidirectional"))
      (node (ref "ULTRASONIC1") (pin "2") (pinfunction "2_2") (pintype "passive"))
    )
    (net (code "76") (name "Net-(B1-Pad26)") (class "Default")
      (node (ref "B1") (pin "26") (pinfunction "26_26") (pintype "bidirectional"))
      (node (ref "DIGITAL_SPARE1") (pin "1") (pinfunction "1_1") (pintype "passive"))
    )
    (net (code "77") (name "Net-(B1-Pad28)") (class "Default")
      (node (ref "B1") (pin "28") (pinfunction "28_28") (pintype "bidirectional"))
      (node (ref "DIGITAL_SPARE1") (pin "2") (pinfunction "2_2") (pintype "passive"))
    )
    (net (code "78") (name "Net-(B1-Pad30)") (class "Default")
      (node (ref "B1") (pin "30") (pinfunction "30_30") (pintype "bidirectional"))
      (node (ref "DIGITAL_SPARE1") (pin "3") (pinfunction "3_3") (pintype "passive"))
    )
    (net (code "79") (name "Net-(B1-Pad32)") (class "Default")
      (node (ref "B1") (pin "32") (pinfunction "32_32") (pintype "bidirectional"))
      (node (ref "DIGITAL_SPARE2") (pin "1") (pinfunction "1_1") (pintype "passive"))
    )
    (net (code "80") (name "Net-(B1-Pad34)") (class "Default")
      (node (ref "B1") (pin "34") (pinfunction "34_34") (pintype "bidirectional"))
      (node (ref "DIGITAL_SPARE2") (pin "2") (pinfunction "2_2") (pintype "passive"))
    )
    (net (code "81") (name "Net-(B1-Pad41)") (class "Default")
      (node (ref "B1") (pin "41") (pinfunction "41_41") (pintype "bidirectional"))
      (node (ref "DIGITAL_SPARE_MEGA1") (pin "7") (pinfunction "7_7") (pintype "passive"))
    )
    (net (code "82") (name "Net-(B1-Pad43)") (class "Default")
      (node (ref "B1") (pin "43") (pinfunction "43_43") (pintype "bidirectional"))
      (node (ref "DIGITAL_SPARE_MEGA1") (pin "6") (pinfunction "6_6") (pintype "passive"))
    )
    (net (code "83") (name "Net-(B1-Pad45)") (class "Default")
      (node (ref "B1") (pin "45") (pinfunction "45_45") (pintype "bidirectional"))
      (node (ref "DIGITAL_SPARE_MEGA1") (pin "5") (pinfunction "5_5") (pintype "passive"))
    )
    (net (code "84") (name "Net-(B1-Pad47)") (class "Default")
      (node (ref "B1") (pin "47") (pinfunction "47_47") (pintype "bidirectional"))
      (node (ref "DIGITAL_SPARE_MEGA1") (pin "4") (pinfunction "4_4") (pintype "passive"))
    )
    (net (code "85") (name "Net-(B1-Pad48)") (class "Default")
      (node (ref "B1") (pin "48") (pinfunction "48_48") (pintype "bidirectional"))
      (node (ref "DIGITAL_SPARE2") (pin "3") (pinfunction "3_3") (pintype "passive"))
    )
    (net (code "86") (name "Net-(B1-Pad49)") (class "Default")
      (node (ref "B1") (pin "49") (pinfunction "49_49") (pintype "bidirectional"))
      (node (ref "DIGITAL_SPARE_MEGA1") (pin "3") (pinfunction "3_3") (pintype "passive"))
    )
    (net (code "87") (name "Net-(B1-PadAREF)") (class "Default")
      (node (ref "B1") (pin "AREF") (pinfunction "AREF_AREF") (pintype "bidirectional"))
      (node (ref "I2C") (pin "3") (pinfunction "3_3") (pintype "passive"))
    )
    (net (code "88") (name "Net-(B1-PadSCL)") (class "Default")
      (node (ref "B1") (pin "SCL") (pinfunction "SCL_SCL") (pintype "bidirectional"))
      (node (ref "I2C") (pin "1") (pinfunction "1_1") (pintype "passive"))
    )
    (net (code "89") (name "Net-(B1-PadSDA)") (class "Default")
      (node (ref "B1") (pin "SDA") (pinfunction "SDA_SDA") (pintype "bidirectional"))
      (node (ref "I2C") (pin "2") (pinfunction "2_2") (pintype "passive"))
    )
    (net (code "90") (name "Net-(D1-PadA)") (class "Default")
      (node (ref "D1") (pin "A") (pinfunction "A_A") (pintype "passive"))
      (node (ref "F4") (pin "2") (pinfunction "2_2") (pintype "passive"))
    )
    (net (code "91") (name "Net-(DIGITAL_SPARE_NANO-Pad1)") (class "Default")
      (node (ref "DIGITAL_SPARE_NANO") (pin "1") (pinfunction "1_1") (pintype "passive"))
      (node (ref "U$1") (pin "D8") (pinfunction "D8_D8") (pintype "bidirectional"))
    )
    (net (code "92") (name "Net-(DIGITAL_SPARE_NANO-Pad2)") (class "Default")
      (node (ref "DIGITAL_SPARE_NANO") (pin "2") (pinfunction "2_2") (pintype "passive"))
      (node (ref "U$1") (pin "D7") (pinfunction "D7_D7") (pintype "bidirectional"))
    )
    (net (code "93") (name "Net-(DIGITAL_SPARE_NANO-Pad3)") (class "Default")
      (node (ref "DIGITAL_SPARE_NANO") (pin "3") (pinfunction "3_3") (pintype "passive"))
      (node (ref "U$1") (pin "D6") (pinfunction "D6_D6") (pintype "bidirectional"))
    )
    (net (code "94") (name "Net-(IMU-Pad5)") (class "Default")
      (node (ref "IMU") (pin "5") (pinfunction "5_5") (pintype "passive"))
      (node (ref "U$1") (pin "A4") (pinfunction "A4_A4") (pintype "bidirectional"))
    )
    (net (code "95") (name "Net-(IMU-Pad6)") (class "Default")
      (node (ref "IMU") (pin "6") (pinfunction "6_6") (pintype "passive"))
      (node (ref "U$1") (pin "A5") (pinfunction "A5_A5") (pintype "bidirectional"))
    )
    (net (code "96") (name "Net-(LED1-PadA)") (class "Default")
      (node (ref "LED1") (pin "A") (pinfunction "A_A") (pintype "passive"))
      (node (ref "R1") (pin "2") (pinfunction "2_2") (pintype "passive"))
    )
    (net (code "97") (name "Net-(LED2-PadA)") (class "Default")
      (node (ref "LED2") (pin "A") (pinfunction "A_A") (pintype "passive"))
      (node (ref "R2") (pin "2") (pinfunction "2_2") (pintype "passive"))
    )
    (net (code "98") (name "Net-(LED3-C)") (class "Default")
      (node (ref "2.21K") (pin "2") (pinfunction "2_2") (pintype "passive"))
      (node (ref "LED3") (pin "K") (pinfunction "C_K") (pintype "passive"))
    )
    (net (code "99") (name "Net-(LED4-C)") (class "Default")
      (node (ref "2.33K") (pin "2") (pinfunction "2_2") (pintype "passive"))
      (node (ref "LED4") (pin "K") (pinfunction "C_K") (pintype "passive"))
    )
    (net (code "100") (name "Net-(LED5-PadA)") (class "Default")
      (node (ref "LED5") (pin "A") (pinfunction "A_A") (pintype "passive"))
      (node (ref "R3") (pin "2") (pinfunction "2_2") (pintype "passive"))
    )
    (net (code "101") (name "Net-(LED6-PadA)") (class "Default")
      (node (ref "LED6") (pin "A") (pinfunction "A_A") (pintype "passive"))
      (node (ref "R4") (pin "2") (pinfunction "2_2") (pintype "passive"))
    )
    (net (code "102") (name "Net-(LED7-PadA)") (class "Default")
      (node (ref "LED7") (pin "A") (pinfunction "A_A") (pintype "passive"))
      (node (ref "R5") (pin "2") (pinfunction "2_2") (pintype "passive"))
    )
    (net (code "103") (name "Net-(LED8-PadA)") (class "Default")
      (node (ref "LED8") (pin "A") (pinfunction "A_A") (pintype "passive"))
      (node (ref "R6") (pin "2") (pinfunction "2_2") (pintype "passive"))
    )
    (net (code "104") (name "Net-(LED9-PadA)") (class "Default")
      (node (ref "LED9") (pin "A") (pinfunction "A_A") (pintype "passive"))
      (node (ref "R7") (pin "2") (pinfunction "2_2") (pintype "passive"))
    )
    (net (code "105") (name "Net-(SERIAL_NANO-Pad1)") (class "Default")
      (node (ref "SERIAL_NANO") (pin "1") (pinfunction "1_1") (pintype "passive"))
      (node (ref "U$1") (pin "RX1") (pinfunction "RX1_RX1") (pintype "bidirectional"))
    )
    (net (code "106") (name "Net-(SERIAL_NANO-Pad2)") (class "Default")
      (node (ref "SERIAL_NANO") (pin "2") (pinfunction "2_2") (pintype "passive"))
      (node (ref "U$1") (pin "TX0") (pinfunction "TX0_TX0") (pintype "bidirectional"))
    )
    (net (code "107") (name "Net-(STATE-C)") (class "Default")
      (node (ref "330") (pin "2") (pinfunction "2_2") (pintype "passive"))
      (node (ref "STATE") (pin "K") (pinfunction "C_K") (pintype "passive"))
    )
    (net (code "108") (name "Net-(U$1-PadD9)") (class "Default")
      (node (ref "U$1") (pin "D9") (pinfunction "D9_D9") (pintype "bidirectional"))
      (node (ref "ULTRASONIC3") (pin "3") (pinfunction "3_3") (pintype "passive"))
    )
    (net (code "109") (name "Net-(U$1-PadD10)") (class "Default")
      (node (ref "U$1") (pin "D10") (pinfunction "D10_D10") (pintype "bidirectional"))
      (node (ref "ULTRASONIC3") (pin "2") (pinfunction "2_2") (pintype "passive"))
    )
    (net (code "110") (name "Net-(U$1-PadD11)") (class "Default")
      (node (ref "U$1") (pin "D11") (pinfunction "D11_D11") (pintype "bidirectional"))
      (node (ref "ULTRASONIC2") (pin "3") (pinfunction "3_3") (pintype "passive"))
    )
    (net (code "111") (name "Net-(U$1-PadD12)") (class "Default")
      (node (ref "U$1") (pin "D12") (pinfunction "D12_D12") (pintype "bidirectional"))
      (node (ref "ULTRASONIC2") (pin "2") (pinfunction "2_2") (pintype "passive"))
    )
    (net (code "112") (name "PWM.A") (class "Default")
      (node (ref "B1") (pin "12") (pinfunction "12_12") (pintype "bidirectional"))
      (node (ref "DRIVER.1") (pin "2") (pinfunction "2_2") (pintype "passive"))
    )
    (net (code "113") (name "PWM.B") (class "Default")
      (node (ref "B1") (pin "11") (pinfunction "11_11") (pintype "bidirectional"))
      (node (ref "DRIVER.1") (pin "4") (pinfunction "4_4") (pintype "passive"))
    )
    (net (code "114") (name "PWM.C") (class "Default")
      (node (ref "B1") (pin "9") (pinfunction "9_9") (pintype "bidirectional"))
      (node (ref "DRIVER.2") (pin "2") (pinfunction "2_2") (pintype "passive"))
    )
    (net (code "115") (name "PWM.D") (class "Default")
      (node (ref "B1") (pin "10") (pinfunction "10_10") (pintype "bidirectional"))
      (node (ref "DRIVER.2") (pin "4") (pinfunction "4_4") (pintype "passive"))
    )
    (net (code "116") (name "PWM.E") (class "Default")
      (node (ref "B1") (pin "8") (pinfunction "8_8") (pintype "bidirectional"))
      (node (ref "DRIVER.3") (pin "2") (pinfunction "2_2") (pintype "passive"))
    )
    (net (code "117") (name "PWM.F") (class "Default")
      (node (ref "B1") (pin "7") (pinfunction "7_7") (pintype "bidirectional"))
      (node (ref "DRIVER.3") (pin "4") (pinfunction "4_4") (pintype "passive"))
    )
    (net (code "118") (name "PWM.G") (class "Default")
      (node (ref "B1") (pin "6") (pinfunction "6_6") (pintype "bidirectional"))
      (node (ref "DRIVER.4") (pin "2") (pinfunction "2_2") (pintype "passive"))
    )
    (net (code "119") (name "PWM.H") (class "Default")
      (node (ref "B1") (pin "4") (pinfunction "4_4") (pintype "bidirectional"))
      (node (ref "DRIVER.4") (pin "4") (pinfunction "4_4") (pintype "passive"))
    )
    (net (code "120") (name "RESET.MEGA") (class "Default")
      (node (ref "1K") (pin "1") (pinfunction "1_1") (pintype "passive"))
      (node (ref "B1") (pin "RESET") (pinfunction "~{RESET}_RESET") (pintype "bidirectional"))
      (node (ref "U$2") (pin "2") (pinfunction "2_2") (pintype "bidirectional"))
    )
    (net (code "121") (name "RX.BLUE") (class "Default")
      (node (ref "1.1K") (pin "1") (pinfunction "1_1") (pintype "passive"))
      (node (ref "2.32K") (pin "2") (pinfunction "2_2") (pintype "passive"))
      (node (ref "BLUETOOTH") (pin "2") (pinfunction "2_2") (pintype "passive"))
    )
    (net (code "122") (name "RX.NANO") (class "Default")
      (node (ref "B1") (pin "16") (pinfunction "16(TX2)_16") (pintype "bidirectional"))
      (node (ref "U$1") (pin "D5") (pinfunction "D5_D5") (pintype "bidirectional"))
    )
    (net (code "123") (name "STATE") (class "Default")
      (node (ref "BLUETOOTH") (pin "1") (pinfunction "1_1") (pintype "passive"))
      (node (ref "STATE") (pin "A") (pinfunction "A_A") (pintype "passive"))
    )
    (net (code "124") (name "TX.BLUE") (class "Default")
      (node (ref "B1") (pin "15") (pinfunction "15(RX3)_15") (pintype "bidirectional"))
      (node (ref "BLUETOOTH") (pin "3") (pinfunction "3_3") (pintype "passive"))
    )
    (net (code "125") (name "TX.MEGA") (class "Default")
      (node (ref "1.1K") (pin "2") (pinfunction "2_2") (pintype "passive"))
      (node (ref "B1") (pin "14") (pinfunction "14(TX3)_14") (pintype "bidirectional"))
    )
    (net (code "126") (name "TX.NANO") (class "Default")
      (node (ref "B1") (pin "17") (pinfunction "17(RX2)_17") (pintype "bidirectional"))
      (node (ref "U$1") (pin "D4") (pinfunction "D4_D4") (pintype "bidirectional"))
    )
    (net (code "127") (name "unconnected-(B1-Pad13)") (class "Default")
      (node (ref "B1") (pin "13") (pinfunction "13_13") (pintype "bidirectional"))
    )
    (net (code "128") (name "unconnected-(B1-Pad22)") (class "Default")
      (node (ref "B1") (pin "22") (pinfunction "22_22") (pintype "bidirectional"))
    )
    (net (code "129") (name "unconnected-(B1-PadIOREF)") (class "Default")
      (node (ref "B1") (pin "IOREF") (pinfunction "IOREF_IOREF") (pintype "bidirectional"))
    )
    (net (code "130") (name "unconnected-(ENCODER.A-Pad3)") (class "Default")
      (node (ref "ENCODER.A") (pin "3") (pinfunction "3_3") (pintype "passive"))
    )
    (net (code "131") (name "unconnected-(ENCODER.A1-Pad3)") (class "Default")
      (node (ref "ENCODER.A1") (pin "3") (pinfunction "3_3") (pintype "passive"))
    )
    (net (code "132") (name "unconnected-(ENCODER.C-Pad3)") (class "Default")
      (node (ref "ENCODER.C") (pin "3") (pinfunction "3_3") (pintype "passive"))
    )
    (net (code "133") (name "unconnected-(ENCODER.C1-Pad3)") (class "Default")
      (node (ref "ENCODER.C1") (pin "3") (pinfunction "3_3") (pintype "passive"))
    )
    (net (code "134") (name "unconnected-(ENCODER.C2-Pad3)") (class "Default")
      (node (ref "ENCODER.C2") (pin "3") (pinfunction "3_3") (pintype "passive"))
    )
    (net (code "135") (name "unconnected-(ENCODER.C3-Pad3)") (class "Default")
      (node (ref "ENCODER.C3") (pin "3") (pinfunction "3_3") (pintype "passive"))
    )
    (net (code "136") (name "unconnected-(IC1A-A-Pad15)") (class "Default")
      (node (ref "IC1") (pin "15") (pinfunction "A_15") (pintype "input"))
    )
    (net (code "137") (name "unconnected-(IC1A-B-Pad1)") (class "Default")
      (node (ref "IC1") (pin "1") (pinfunction "B_1") (pintype "input"))
    )
    (net (code "138") (name "unconnected-(IC1A-BO-Pad13)") (class "Default")
      (node (ref "IC1") (pin "13") (pinfunction "BO_13") (pintype "output"))
    )
    (net (code "139") (name "unconnected-(IC1A-C-Pad10)") (class "Default")
      (node (ref "IC1") (pin "10") (pinfunction "C_10") (pintype "input"))
    )
    (net (code "140") (name "unconnected-(IC1A-D-Pad9)") (class "Default")
      (node (ref "IC1") (pin "9") (pinfunction "D_9") (pintype "input"))
    )
    (net (code "141") (name "unconnected-(IC1A-QA-Pad3)") (class "Default")
      (node (ref "IC1") (pin "3") (pinfunction "QA_3") (pintype "output"))
    )
    (net (code "142") (name "unconnected-(IC1A-QB-Pad2)") (class "Default")
      (node (ref "IC1") (pin "2") (pinfunction "QB_2") (pintype "output"))
    )
    (net (code "143") (name "unconnected-(IC1A-QC-Pad6)") (class "Default")
      (node (ref "IC1") (pin "6") (pinfunction "QC_6") (pintype "output"))
    )
    (net (code "144") (name "unconnected-(IC1A-QD-Pad7)") (class "Default")
      (node (ref "IC1") (pin "7") (pinfunction "QD_7") (pintype "output"))
    )
    (net (code "145") (name "unconnected-(IC2A-A-Pad15)") (class "Default")
      (node (ref "IC2") (pin "15") (pinfunction "A_15") (pintype "input"))
    )
    (net (code "146") (name "unconnected-(IC2A-B-Pad1)") (class "Default")
      (node (ref "IC2") (pin "1") (pinfunction "B_1") (pintype "input"))
    )
    (net (code "147") (name "unconnected-(IC2A-BO-Pad13)") (class "Default")
      (node (ref "IC2") (pin "13") (pinfunction "BO_13") (pintype "output"))
    )
    (net (code "148") (name "unconnected-(IC2A-C-Pad10)") (class "Default")
      (node (ref "IC2") (pin "10") (pinfunction "C_10") (pintype "input"))
    )
    (net (code "149") (name "unconnected-(IC2A-D-Pad9)") (class "Default")
      (node (ref "IC2") (pin "9") (pinfunction "D_9") (pintype "input"))
    )
    (net (code "150") (name "unconnected-(IC2A-QA-Pad3)") (class "Default")
      (node (ref "IC2") (pin "3") (pinfunction "QA_3") (pintype "output"))
    )
    (net (code "151") (name "unconnected-(IC2A-QB-Pad2)") (class "Default")
      (node (ref "IC2") (pin "2") (pinfunction "QB_2") (pintype "output"))
    )
    (net (code "152") (name "unconnected-(IC2A-QC-Pad6)") (class "Default")
      (node (ref "IC2") (pin "6") (pinfunction "QC_6") (pintype "output"))
    )
    (net (code "153") (name "unconnected-(IC2A-QD-Pad7)") (class "Default")
      (node (ref "IC2") (pin "7") (pinfunction "QD_7") (pintype "output"))
    )
    (net (code "154") (name "unconnected-(IC3A-A-Pad15)") (class "Default")
      (node (ref "IC3") (pin "15") (pinfunction "A_15") (pintype "input"))
    )
    (net (code "155") (name "unconnected-(IC3A-B-Pad1)") (class "Default")
      (node (ref "IC3") (pin "1") (pinfunction "B_1") (pintype "input"))
    )
    (net (code "156") (name "unconnected-(IC3A-BO-Pad13)") (class "Default")
      (node (ref "IC3") (pin "13") (pinfunction "BO_13") (pintype "output"))
    )
    (net (code "157") (name "unconnected-(IC3A-C-Pad10)") (class "Default")
      (node (ref "IC3") (pin "10") (pinfunction "C_10") (pintype "input"))
    )
    (net (code "158") (name "unconnected-(IC3A-D-Pad9)") (class "Default")
      (node (ref "IC3") (pin "9") (pinfunction "D_9") (pintype "input"))
    )
    (net (code "159") (name "unconnected-(IC3A-QA-Pad3)") (class "Default")
      (node (ref "IC3") (pin "3") (pinfunction "QA_3") (pintype "output"))
    )
    (net (code "160") (name "unconnected-(IC3A-QB-Pad2)") (class "Default")
      (node (ref "IC3") (pin "2") (pinfunction "QB_2") (pintype "output"))
    )
    (net (code "161") (name "unconnected-(IC3A-QC-Pad6)") (class "Default")
      (node (ref "IC3") (pin "6") (pinfunction "QC_6") (pintype "output"))
    )
    (net (code "162") (name "unconnected-(IC3A-QD-Pad7)") (class "Default")
      (node (ref "IC3") (pin "7") (pinfunction "QD_7") (pintype "output"))
    )
    (net (code "163") (name "unconnected-(IC4A-A-Pad15)") (class "Default")
      (node (ref "IC4") (pin "15") (pinfunction "A_15") (pintype "input"))
    )
    (net (code "164") (name "unconnected-(IC4A-B-Pad1)") (class "Default")
      (node (ref "IC4") (pin "1") (pinfunction "B_1") (pintype "input"))
    )
    (net (code "165") (name "unconnected-(IC4A-BO-Pad13)") (class "Default")
      (node (ref "IC4") (pin "13") (pinfunction "BO_13") (pintype "output"))
    )
    (net (code "166") (name "unconnected-(IC4A-C-Pad10)") (class "Default")
      (node (ref "IC4") (pin "10") (pinfunction "C_10") (pintype "input"))
    )
    (net (code "167") (name "unconnected-(IC4A-D-Pad9)") (class "Default")
      (node (ref "IC4") (pin "9") (pinfunction "D_9") (pintype "input"))
    )
    (net (code "168") (name "unconnected-(IC4A-QA-Pad3)") (class "Default")
      (node (ref "IC4") (pin "3") (pinfunction "QA_3") (pintype "output"))
    )
    (net (code "169") (name "unconnected-(IC4A-QB-Pad2)") (class "Default")
      (node (ref "IC4") (pin "2") (pinfunction "QB_2") (pintype "output"))
    )
    (net (code "170") (name "unconnected-(IC4A-QC-Pad6)") (class "Default")
      (node (ref "IC4") (pin "6") (pinfunction "QC_6") (pintype "output"))
    )
    (net (code "171") (name "unconnected-(IC4A-QD-Pad7)") (class "Default")
      (node (ref "IC4") (pin "7") (pinfunction "QD_7") (pintype "output"))
    )
    (net (code "172") (name "unconnected-(IMU-Pad2)") (class "Default")
      (node (ref "IMU") (pin "2") (pinfunction "2_2") (pintype "passive"))
    )
    (net (code "173") (name "unconnected-(IMU-Pad3)") (class "Default")
      (node (ref "IMU") (pin "3") (pinfunction "3_3") (pintype "passive"))
    )
    (net (code "174") (name "unconnected-(IMU-Pad4)") (class "Default")
      (node (ref "IMU") (pin "4") (pinfunction "4_4") (pintype "passive"))
    )
    (net (code "175") (name "unconnected-(U$1-PadAREF)") (class "Default")
      (node (ref "U$1") (pin "AREF") (pinfunction "AREF_AREF") (pintype "bidirectional"))
    )
    (net (code "176") (name "unconnected-(U$1-PadD13)") (class "Default")
      (node (ref "U$1") (pin "D13") (pinfunction "D13_D13") (pintype "bidirectional"))
    )
    (net (code "177") (name "unconnected-(U$1-PadRST)") (class "Default")
      (node (ref "U$1") (pin "RST") (pinfunction "RST_RST") (pintype "bidirectional"))
    )
    (net (code "178") (name "unconnected-(U$1-PadRST1)") (class "Default")
      (node (ref "U$1") (pin "RST1") (pinfunction "RST1_RST1") (pintype "bidirectional"))
    )
  )
)
